# Power.net
KiCad netlist of a schematic drawn in Altium Designer
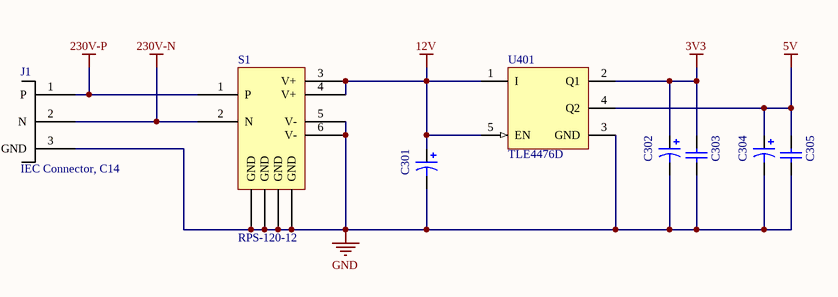
[diagram p0: Power.SchDoc]

(export (version "E")
  (design (tool "Eeschema 10.0.6"))
  (components
    (comp (ref "C301")
      (value "T491B")
      (footprint "B")
      (description "Solid Tantalum Chip Capacitor, Standard T491 Series - Industrial Grade")
      (fields (field (name "PUBLISHER") "Altium Limited"))
      (libsource (lib "KEMET Chip Capacitor") (part "T491B"))
    )
    (comp (ref "C302")
      (value "T491B")
      (footprint "B")
      (description "Solid Tantalum Chip Capacitor, Standard T491 Series - Industrial Grade")
      (fields (field (name "PUBLISHER") "Altium Limited"))
      (libsource (lib "KEMET Chip Capacitor") (part "T491B"))
    )
    (comp (ref "C303")
      (value "CAP 100nF 10V 1206(3216)")
      (footprint "CAPC1206(3216)190_M")
      (description "CAP 100nF 10V ±5% 1206 (3216 Metric) Thickness 1.9mm SMD")
      (fields (field (name "TOLERANCE") "Â±5%"))
      (libsource (lib "Altium Content Vault") (part "CMP-1037-04171-1"))
    )
    (comp (ref "C304")
      (value "T491B")
      (footprint "B")
      (description "Solid Tantalum Chip Capacitor, Standard T491 Series - Industrial Grade")
      (fields (field (name "PUBLISHER") "Altium Limited"))
      (libsource (lib "KEMET Chip Capacitor") (part "T491B"))
    )
    (comp (ref "C305")
      (value "CAP 100nF 10V 1206(3216)")
      (footprint "CAPC1206(3216)190_M")
      (description "CAP 100nF 10V ±5% 1206 (3216 Metric) Thickness 1.9mm SMD")
      (fields (field (name "TOLERANCE") "Â±5%"))
      (libsource (lib "Altium Content Vault") (part "CAP"))
    )
    (comp (ref "J1")
      (value "IEC Connector, C14")
      (footprint "PX0580")
      (description "IEC C14, Right Angle Male, Mounting Holes")
      (libsource (lib "CNC_Control") (part "PX0580/PC/12132"))
    )
    (comp (ref "S1")
      (value "RPS-120-12")
      (footprint "RPS-120-12")
      (description "Power supply, 120 W, 12V/10A, unenclosed")
      (libsource (lib "CNC_Control") (part "RPS-120-12"))
    )
    (comp (ref "U401")
      (value "TLE4476D")
      (footprint "INF-PG-TO252-5-11_N")
      (fields (field (name "MANUFACTURER") "Infineon"))
      (libsource (lib "Altium Content Vault") (part "INF-TLE4476D-PG-TO252-5-11-5"))
    )
  )
  (nets
    (net (code "1") (name "3V3") (class "Default")
      (node (ref "C302") (pin "1") (pinfunction "1_1") (pintype "passive"))
      (node (ref "C303") (pin "2") (pinfunction "2_2") (pintype "passive"))
      (node (ref "U401") (pin "2") (pinfunction "Q1_2") (pintype "power_in"))
    )
    (net (code "2") (name "5V") (class "Default")
      (node (ref "C304") (pin "1") (pinfunction "1_1") (pintype "passive"))
      (node (ref "C305") (pin "2") (pinfunction "2_2") (pintype "passive"))
      (node (ref "U401") (pin "4") (pinfunction "Q2_4") (pintype "power_in"))
    )
    (net (code "3") (name "12V") (class "Default")
      (node (ref "C301") (pin "1") (pinfunction "1_1") (pintype "passive"))
      (node (ref "S1") (pin "3") (pinfunction "V+_3") (pintype "passive"))
      (node (ref "S1") (pin "4") (pinfunction "V+_4") (pintype "passive"))
      (node (ref "U401") (pin "1") (pinfunction "I_1") (pintype "power_in"))
      (node (ref "U401") (pin "5") (pinfunction "EN_5") (pintype "input"))
    )
    (net (code "4") (name "230V-N") (class "Default")
      (node (ref "J1") (pin "2") (pinfunction "N_2") (pintype "power_in"))
      (node (ref "S1") (pin "2") (pinfunction "N_2") (pintype "power_in"))
    )
    (net (code "5") (name "230V-P") (class "Default")
      (node (ref "J1") (pin "1") (pinfunction "P_1") (pintype "power_in"))
      (node (ref "S1") (pin "1") (pinfunction "P_1") (pintype "power_in"))
    )
    (net (code "6") (name "GND") (class "Default")
      (node (ref "C301") (pin "2") (pinfunction "2_2") (pintype "passive"))
      (node (ref "C302") (pin "2") (pinfunction "2_2") (pintype "passive"))
      (node (ref "C303") (pin "1") (pinfunction "1_1") (pintype "passive"))
      (node (ref "C304") (pin "2") (pinfunction "2_2") (pintype "passive"))
      (node (ref "C305") (pin "1") (pinfunction "1_1") (pintype "passive"))
      (node (ref "J1") (pin "3") (pinfunction "GND_3") (pintype "power_in"))
      (node (ref "S1") (pin "5") (pinfunction "V-_5") (pintype "passive"))
      (node (ref "S1") (pin "6") (pinfunction "V-_6") (pintype "passive"))
      (node (ref "S1") (pin "H1") (pinfunction "GND_H1") (pintype "passive"))
      (node (ref "S1") (pin "H2") (pinfunction "GND_H2") (pintype "passive"))
      (node (ref "S1") (pin "H3") (pinfunction "GND_H3") (pintype "passive"))
      (node (ref "S1") (pin "H4") (pinfunction "GND_H4") (pintype "passive"))
      (node (ref "U401") (pin "3") (pinfunction "GND_3") (pintype "power_in"))
    )
  )
)
